# Speed_Controller.net
KiCad netlist of a schematic drawn in Altium Designer
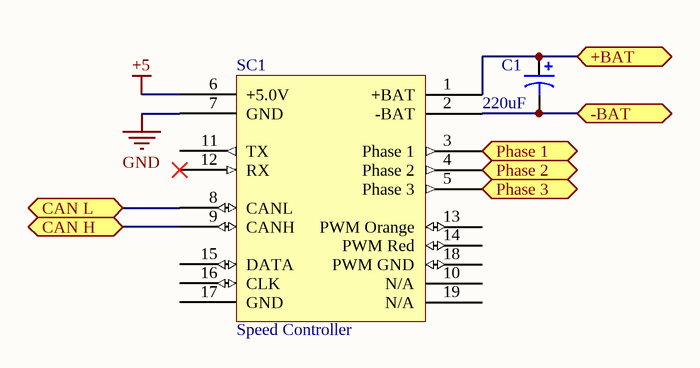
[diagram p0: Speed Controller.SchDoc]

(export (version "E")
  (design (tool "Eeschema 10.0.6"))
  (components
    (comp (ref "C1")
      (value "220uF")
      (footprint "220uf radial Capacitor")
      (description "Polarized Capacitor (Radial)")
      (fields (field (name "Comment") "Cap Pol1") (field (name "PUBLISHER") "Altium Limited"))
      (libsource (lib "Miscellaneous Devices") (part "Cap Pol1"))
    )
    (comp (ref "SC1")
      (value "Speed Controller")
      (footprint "Autoquad-esc32-speed-controller")
      (description "Autoquad ESC32 Speed Controller")
      (libsource (lib "autoquad-esc32-speed-controller") (part "Speed Controller"))
    )
  )
  (nets
    (net (code "1") (name "+5") (class "Default")
      (node (ref "SC1") (pin "6") (pinfunction "+5.0V_6") (pintype "power_in"))
    )
    (net (code "2") (name "/+BAT") (class "Default")
      (node (ref "C1") (pin "1") (pinfunction "1_1") (pintype "passive"))
      (node (ref "SC1") (pin "1") (pinfunction "+BAT_1") (pintype "power_in"))
    )
    (net (code "3") (name "/-BAT") (class "Default")
      (node (ref "C1") (pin "2") (pinfunction "2_2") (pintype "passive"))
      (node (ref "SC1") (pin "2") (pinfunction "-BAT_2") (pintype "power_in"))
    )
    (net (code "4") (name "/CAN H") (class "Default")
      (node (ref "SC1") (pin "9") (pinfunction "CANH_9") (pintype "bidirectional"))
    )
    (net (code "5") (name "/CAN L") (class "Default")
      (node (ref "SC1") (pin "8") (pinfunction "CANL_8") (pintype "bidirectional"))
    )
    (net (code "6") (name "/Phase 1") (class "Default")
      (node (ref "SC1") (pin "3") (pinfunction "Phase_1_3") (pintype "output"))
    )
    (net (code "7") (name "/Phase 2") (class "Default")
      (node (ref "SC1") (pin "4") (pinfunction "Phase_2_4") (pintype "output"))
    )
    (net (code "8") (name "/Phase 3") (class "Default")
      (node (ref "SC1") (pin "5") (pinfunction "Phase_3_5") (pintype "output"))
    )
    (net (code "9") (name "GND") (class "Default")
      (node (ref "SC1") (pin "7") (pinfunction "GND_7") (pintype "power_in"))
    )
    (net (code "10") (name "unconnected-(SC1-CLK-Pad16)") (class "Default")
      (node (ref "SC1") (pin "16") (pinfunction "CLK_16") (pintype "bidirectional"))
    )
    (net (code "11") (name "unconnected-(SC1-DATA-Pad15)") (class "Default")
      (node (ref "SC1") (pin "15") (pinfunction "DATA_15") (pintype "bidirectional"))
    )
    (net (code "12") (name "unconnected-(SC1-GND-Pad17)") (class "Default")
      (node (ref "SC1") (pin "17") (pinfunction "GND_17") (pintype "power_in"))
    )
    (net (code "13") (name "unconnected-(SC1-N{slash}A-Pad10)") (class "Default")
      (node (ref "SC1") (pin "10") (pinfunction "N/A_10") (pintype "passive"))
    )
    (net (code "14") (name "unconnected-(SC1-N{slash}A-Pad19)") (class "Default")
      (node (ref "SC1") (pin "19") (pinfunction "N/A_19") (pintype "passive"))
    )
    (net (code "15") (name "unconnected-(SC1-PWM_GND-Pad18)") (class "Default")
      (node (ref "SC1") (pin "18") (pinfunction "PWM_GND_18") (pintype "bidirectional"))
    )
    (net (code "16") (name "unconnected-(SC1-PWM_Orange-Pad13)") (class "Default")
      (node (ref "SC1") (pin "13") (pinfunction "PWM_Orange_13") (pintype "bidirectional"))
    )
    (net (code "17") (name "unconnected-(SC1-PWM_Red-Pad14)") (class "Default")
      (node (ref "SC1") (pin "14") (pinfunction "PWM_Red_14") (pintype "bidirectional"))
    )
    (net (code "18") (name "unconnected-(SC1-RX-Pad12)") (class "Default")
      (node (ref "SC1") (pin "12") (pinfunction "RX_12") (pintype "input+no_connect"))
    )
    (net (code "19") (name "unconnected-(SC1-TX-Pad11)") (class "Default")
      (node (ref "SC1") (pin "11") (pinfunction "TX_11") (pintype "output"))
    )
  )
)
